# Stepper_driver.net
KiCad netlist of a schematic drawn in Altium Designer
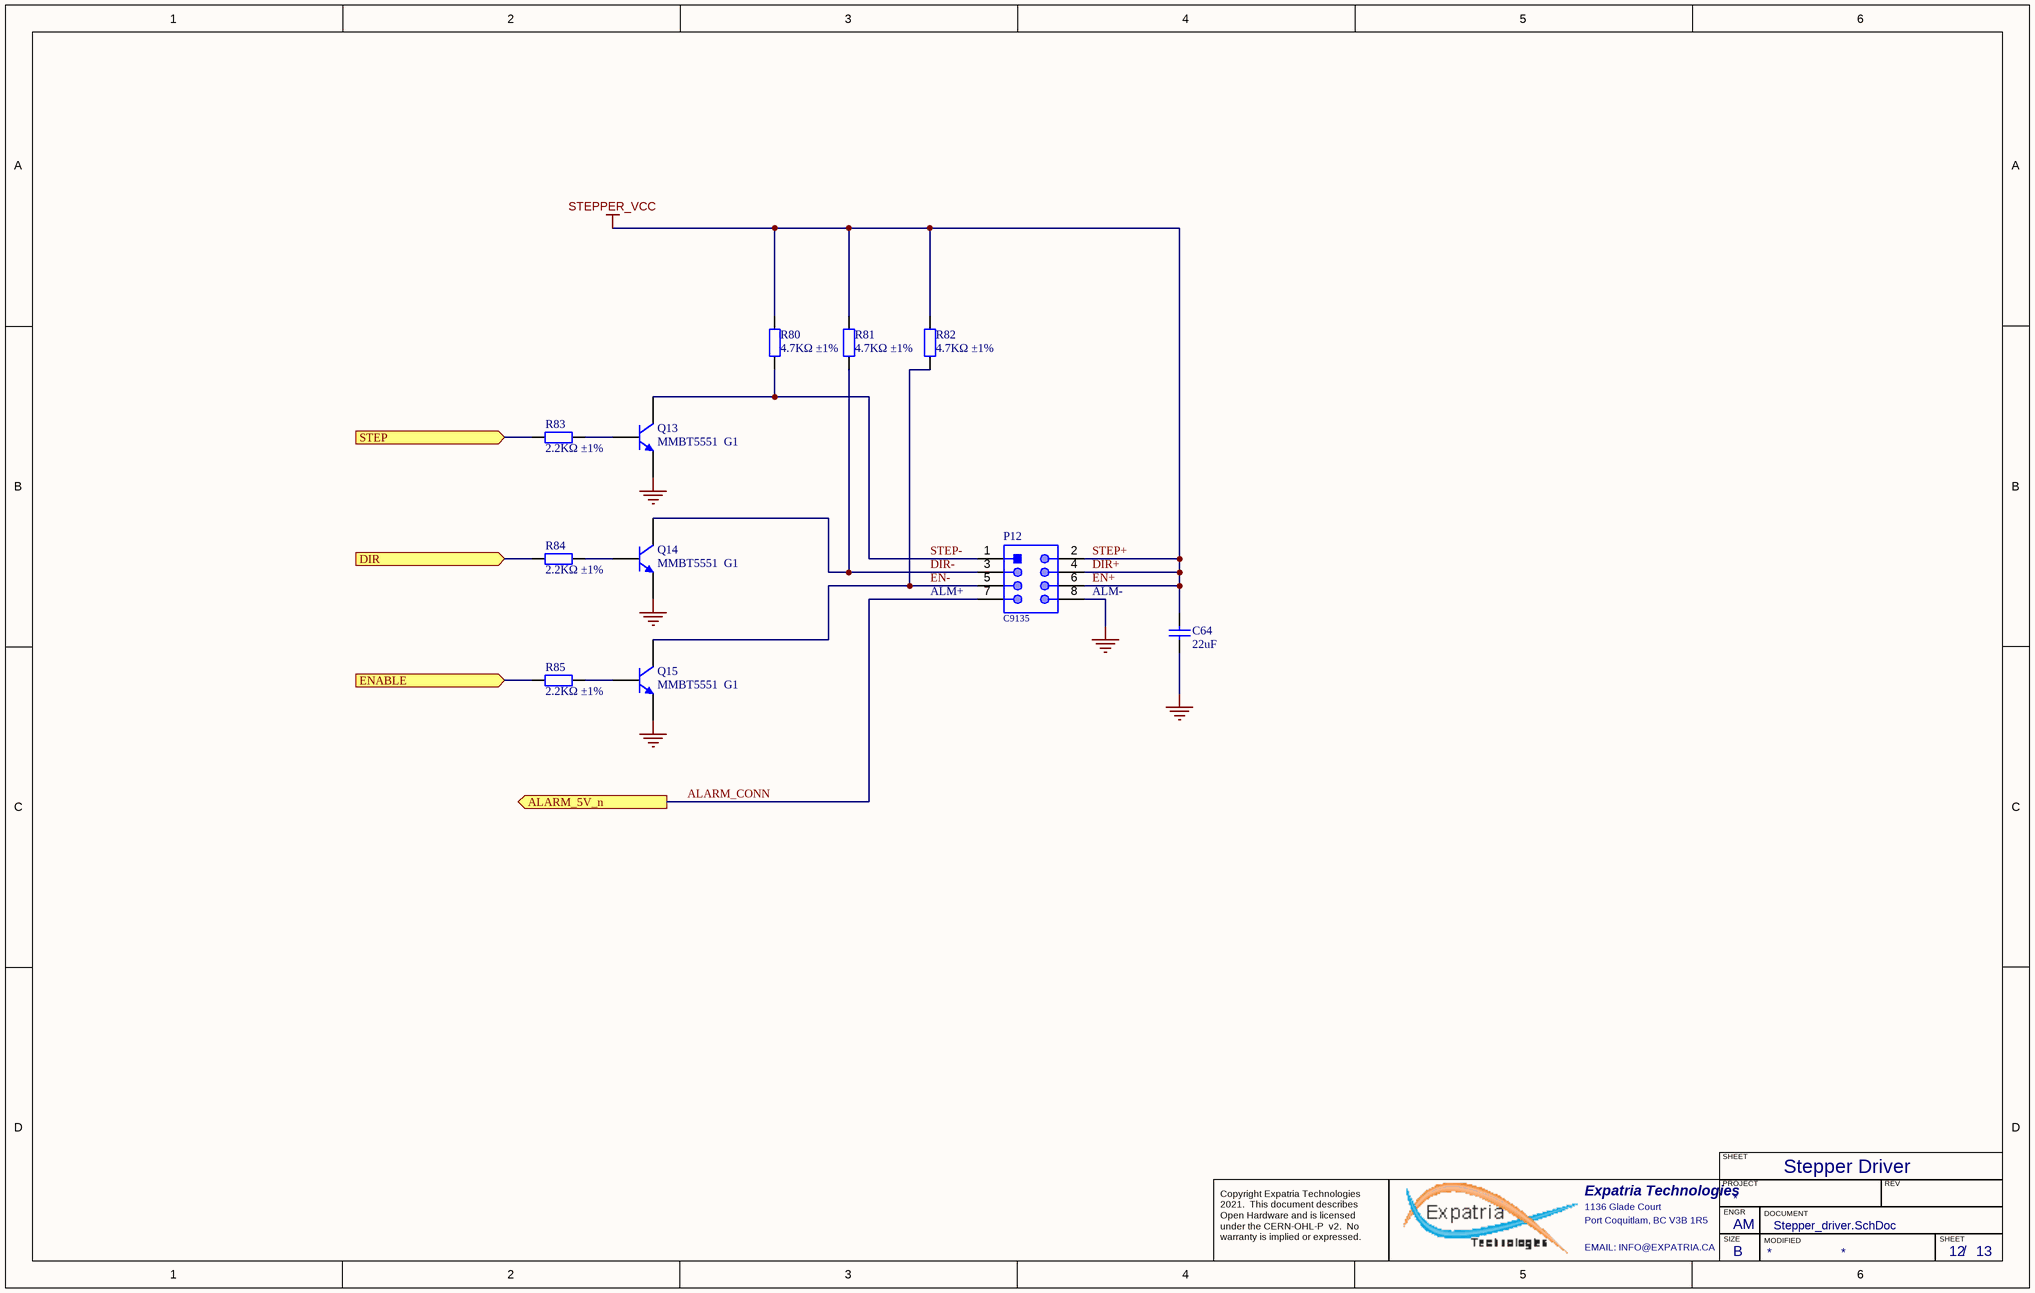
[diagram p0: Stepper_driver.SchDoc]

(export (version "E")
  (design (tool "Eeschema 10.0.6"))
  (components
    (comp (ref "C64")
      (value "22uF")
      (footprint "0805_C")
      (description "Chip capacitors")
      (fields
        (field (name "MANUFACTURER") "Samsung Electro-Mechanics")
        (field (name "PARTNUMBER") "CL21A226MAQNNNE")
      )
      (libsource (lib "Cap") (part "0805 22uF (226) 20% 25V"))
    )
    (comp (ref "P12")
      (value "C9135")
      (footprint "61200821621")
      (description "Male Box Header WR-BHD, THT, Vertical, pitch 2.54 mm, 8 pins")
      (fields (field (name "MANUFACTURER") "Wurth Elektronik") (field (name "PUBLISHER") "WurthElektronik"))
      (libsource (lib "Altium Content Vault") (part "WE-CN-2P-M-R8"))
    )
    (comp (ref "Q13")
      (value "MMBT5551  G1")
      (footprint "SOT-23(SOT-23-3)")
      (description "三极管")
      (libsource (lib "Transistor_NPN") (part "SOT-23 MMBT5551  G1"))
    )
    (comp (ref "Q14")
      (value "MMBT5551  G1")
      (footprint "SOT-23(SOT-23-3)")
      (description "三极管")
      (libsource (lib "Transistor_NPN") (part "SOT-23 MMBT5551  G1"))
    )
    (comp (ref "Q15")
      (value "MMBT5551  G1")
      (footprint "SOT-23(SOT-23-3)")
      (description "三极管")
      (libsource (lib "Transistor_NPN") (part "SOT-23 MMBT5551  G1"))
    )
    (comp (ref "R80")
      (value "4.7KΩ ±1%")
      (footprint "0402_R")
      (description "Chip resistor")
      (fields (field (name "MANUFACTURER") "Uniroyal Elec") (field (name "PARTNUMBER") "0402WGF4701TCE"))
      (libsource (lib "RES") (part "0402 4.7K (4701) 1%"))
    )
    (comp (ref "R81")
      (value "4.7KΩ ±1%")
      (footprint "0402_R")
      (description "Chip resistor")
      (fields (field (name "MANUFACTURER") "Uniroyal Elec") (field (name "PARTNUMBER") "0402WGF4701TCE"))
      (libsource (lib "RES") (part "0402 4.7K (4701) 1%"))
    )
    (comp (ref "R82")
      (value "4.7KΩ ±1%")
      (footprint "0402_R")
      (description "Chip resistor")
      (fields (field (name "MANUFACTURER") "Uniroyal Elec") (field (name "PARTNUMBER") "0402WGF4701TCE"))
      (libsource (lib "RES") (part "0402 4.7K (4701) 1%"))
    )
    (comp (ref "R83")
      (value "2.2KΩ ±1%")
      (footprint "0402_R")
      (description "Chip resistor")
      (fields (field (name "MANUFACTURER") "Uniroyal Elec") (field (name "PARTNUMBER") "0402WGF2201TCE"))
      (libsource (lib "RES") (part "0402 2.2K (2201) 1%"))
    )
    (comp (ref "R84")
      (value "2.2KΩ ±1%")
      (footprint "0402_R")
      (description "Chip resistor")
      (fields (field (name "MANUFACTURER") "Uniroyal Elec") (field (name "PARTNUMBER") "0402WGF2201TCE"))
      (libsource (lib "RES") (part "0402 2.2K (2201) 1%"))
    )
    (comp (ref "R85")
      (value "2.2KΩ ±1%")
      (footprint "0402_R")
      (description "Chip resistor")
      (fields (field (name "MANUFACTURER") "Uniroyal Elec") (field (name "PARTNUMBER") "0402WGF2201TCE"))
      (libsource (lib "RES") (part "0402 2.2K (2201) 1%"))
    )
  )
  (nets
    (net (code "1") (name "/ALARM_CONN") (class "Default")
      (node (ref "P12") (pin "7") (pinfunction "7_7") (pintype "passive"))
    )
    (net (code "2") (name "/DIR") (class "Default")
      (node (ref "R84") (pin "1") (pinfunction "1_1") (pintype "passive"))
    )
    (net (code "3") (name "/DIR-") (class "Default")
      (node (ref "P12") (pin "3") (pinfunction "3_3") (pintype "passive"))
      (node (ref "Q14") (pin "3") (pinfunction "C_3") (pintype "passive"))
      (node (ref "R81") (pin "1") (pinfunction "1_1") (pintype "passive"))
    )
    (net (code "4") (name "/EN-") (class "Default")
      (node (ref "P12") (pin "5") (pinfunction "5_5") (pintype "passive"))
      (node (ref "Q15") (pin "3") (pinfunction "C_3") (pintype "passive"))
      (node (ref "R82") (pin "1") (pinfunction "1_1") (pintype "passive"))
    )
    (net (code "5") (name "/ENABLE") (class "Default")
      (node (ref "R85") (pin "1") (pinfunction "1_1") (pintype "passive"))
    )
    (net (code "6") (name "/STEP") (class "Default")
      (node (ref "R83") (pin "1") (pinfunction "1_1") (pintype "passive"))
    )
    (net (code "7") (name "/STEP-") (class "Default")
      (node (ref "P12") (pin "1") (pinfunction "1_1") (pintype "passive"))
      (node (ref "Q13") (pin "3") (pinfunction "C_3") (pintype "passive"))
      (node (ref "R80") (pin "1") (pinfunction "1_1") (pintype "passive"))
    )
    (net (code "8") (name "GND") (class "Default")
      (node (ref "C64") (pin "1") (pinfunction "1_1") (pintype "passive"))
      (node (ref "P12") (pin "8") (pinfunction "8_8") (pintype "passive"))
      (node (ref "Q13") (pin "2") (pinfunction "E_2") (pintype "passive"))
      (node (ref "Q14") (pin "2") (pinfunction "E_2") (pintype "passive"))
      (node (ref "Q15") (pin "2") (pinfunction "E_2") (pintype "passive"))
    )
    (net (code "9") (name "Net-(Q13-B)") (class "Default")
      (node (ref "Q13") (pin "1") (pinfunction "B_1") (pintype "passive"))
      (node (ref "R83") (pin "2") (pinfunction "2_2") (pintype "passive"))
    )
    (net (code "10") (name "Net-(Q14-B)") (class "Default")
      (node (ref "Q14") (pin "1") (pinfunction "B_1") (pintype "passive"))
      (node (ref "R84") (pin "2") (pinfunction "2_2") (pintype "passive"))
    )
    (net (code "11") (name "Net-(Q15-B)") (class "Default")
      (node (ref "Q15") (pin "1") (pinfunction "B_1") (pintype "passive"))
      (node (ref "R85") (pin "2") (pinfunction "2_2") (pintype "passive"))
    )
    (net (code "12") (name "STEPPER_VCC") (class "Default")
      (node (ref "C64") (pin "2") (pinfunction "2_2") (pintype "passive"))
      (node (ref "P12") (pin "2") (pinfunction "2_2") (pintype "passive"))
      (node (ref "P12") (pin "4") (pinfunction "4_4") (pintype "passive"))
      (node (ref "P12") (pin "6") (pinfunction "6_6") (pintype "passive"))
      (node (ref "R80") (pin "2") (pinfunction "2_2") (pintype "passive"))
      (node (ref "R81") (pin "2") (pinfunction "2_2") (pintype "passive"))
      (node (ref "R82") (pin "2") (pinfunction "2_2") (pintype "passive"))
    )
  )
)
